# LCDv.net
KiCad netlist of a schematic drawn in EAGLE
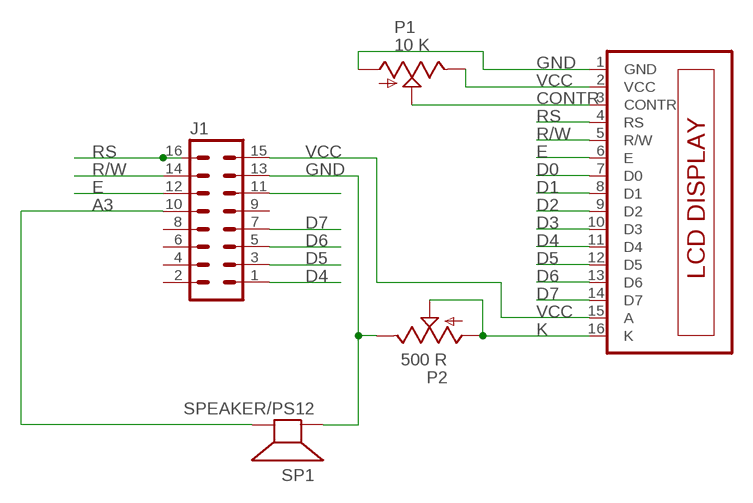
[diagram p0: schematic, sheet 1]

(export (version "E")
  (design (tool "Eeschema 10.0.6"))
  (components
    (comp (ref "J1")
      (value "ML16L")
      (footprint "eagle-import:ML16L")
      (libsource (lib "eagle-import") (part "ML16L"))
    )
    (comp (ref "LCD1")
      (value "DISP_LCD-4X20")
      (footprint "eagle-import:DISP_LCD_4X20")
      (libsource (lib "eagle-import") (part "DISP_LCD-4X20"))
    )
    (comp (ref "P1")
      (value "10 K")
      (footprint "eagle-import:6MM")
      (libsource (lib "eagle-import") (part "TRIM"))
    )
    (comp (ref "P2")
      (value "500 R")
      (footprint "eagle-import:6MM")
      (libsource (lib "eagle-import") (part "TRIM"))
    )
    (comp (ref "SP1")
      (value "SPEAKER/PS12")
      (footprint "eagle-import:PS12")
      (libsource (lib "eagle-import") (part "SPEAKER/PS12"))
    )
  )
  (nets
    (net (code "1") (name "/A3") (class "Default")
      (node (ref "J1") (pin "10") (pinfunction "10_10") (pintype "passive"))
      (node (ref "SP1") (pin "P$2") (pinfunction "-_P$2") (pintype "passive"))
    )
    (net (code "2") (name "/CONTR") (class "Default")
      (node (ref "LCD1") (pin "3") (pinfunction "CONTR_3") (pintype "input"))
      (node (ref "P1") (pin "S") (pinfunction "S_S") (pintype "passive"))
    )
    (net (code "3") (name "/D0") (class "Default")
      (node (ref "LCD1") (pin "7") (pinfunction "D0_7") (pintype "input"))
    )
    (net (code "4") (name "/D1") (class "Default")
      (node (ref "LCD1") (pin "8") (pinfunction "D1_8") (pintype "input"))
    )
    (net (code "5") (name "/D2") (class "Default")
      (node (ref "LCD1") (pin "9") (pinfunction "D2_9") (pintype "input"))
    )
    (net (code "6") (name "/D3") (class "Default")
      (node (ref "LCD1") (pin "10") (pinfunction "D3_10") (pintype "input"))
    )
    (net (code "7") (name "/D4") (class "Default")
      (node (ref "J1") (pin "1") (pinfunction "1_1") (pintype "passive"))
      (node (ref "LCD1") (pin "11") (pinfunction "D4_11") (pintype "input"))
    )
    (net (code "8") (name "/D5") (class "Default")
      (node (ref "J1") (pin "3") (pinfunction "3_3") (pintype "passive"))
      (node (ref "LCD1") (pin "12") (pinfunction "D5_12") (pintype "input"))
    )
    (net (code "9") (name "/D6") (class "Default")
      (node (ref "J1") (pin "5") (pinfunction "5_5") (pintype "passive"))
      (node (ref "LCD1") (pin "13") (pinfunction "D6_13") (pintype "input"))
    )
    (net (code "10") (name "/D7") (class "Default")
      (node (ref "J1") (pin "7") (pinfunction "7_7") (pintype "passive"))
      (node (ref "LCD1") (pin "14") (pinfunction "D7_14") (pintype "input"))
    )
    (net (code "11") (name "/E") (class "Default")
      (node (ref "J1") (pin "12") (pinfunction "12_12") (pintype "passive"))
      (node (ref "LCD1") (pin "6") (pinfunction "E_6") (pintype "input"))
    )
    (net (code "12") (name "/GND") (class "Default")
      (node (ref "J1") (pin "13") (pinfunction "13_13") (pintype "passive"))
      (node (ref "LCD1") (pin "1") (pinfunction "GND_1") (pintype "power_in"))
      (node (ref "P1") (pin "A") (pinfunction "A_A") (pintype "passive"))
      (node (ref "P2") (pin "E") (pinfunction "E_E") (pintype "passive"))
      (node (ref "SP1") (pin "P$1") (pinfunction "+_P$1") (pintype "passive"))
    )
    (net (code "13") (name "/K") (class "Default")
      (node (ref "LCD1") (pin "16") (pinfunction "K_16") (pintype "power_in"))
      (node (ref "P2") (pin "A") (pinfunction "A_A") (pintype "passive"))
      (node (ref "P2") (pin "S") (pinfunction "S_S") (pintype "passive"))
    )
    (net (code "14") (name "/RS") (class "Default")
      (node (ref "J1") (pin "16") (pinfunction "16_16") (pintype "passive"))
      (node (ref "LCD1") (pin "4") (pinfunction "RS_4") (pintype "input"))
    )
    (net (code "15") (name "/R{slash}W") (class "Default")
      (node (ref "J1") (pin "14") (pinfunction "14_14") (pintype "passive"))
      (node (ref "LCD1") (pin "5") (pinfunction "R/W_5") (pintype "input"))
    )
    (net (code "16") (name "/VCC") (class "Default")
      (node (ref "J1") (pin "15") (pinfunction "15_15") (pintype "passive"))
      (node (ref "LCD1") (pin "15") (pinfunction "A_15") (pintype "power_in"))
      (node (ref "LCD1") (pin "2") (pinfunction "VCC_2") (pintype "power_in"))
      (node (ref "P1") (pin "E") (pinfunction "E_E") (pintype "passive"))
    )
    (net (code "17") (name "unconnected-(J1-Pad2)") (class "Default")
      (node (ref "J1") (pin "2") (pinfunction "2_2") (pintype "passive"))
    )
    (net (code "18") (name "unconnected-(J1-Pad4)") (class "Default")
      (node (ref "J1") (pin "4") (pinfunction "4_4") (pintype "passive"))
    )
    (net (code "19") (name "unconnected-(J1-Pad6)") (class "Default")
      (node (ref "J1") (pin "6") (pinfunction "6_6") (pintype "passive"))
    )
    (net (code "20") (name "unconnected-(J1-Pad8)") (class "Default")
      (node (ref "J1") (pin "8") (pinfunction "8_8") (pintype "passive"))
    )
    (net (code "21") (name "unconnected-(J1-Pad9)") (class "Default")
      (node (ref "J1") (pin "9") (pinfunction "9_9") (pintype "passive"))
    )
    (net (code "22") (name "unconnected-(J1-Pad11)") (class "Default")
      (node (ref "J1") (pin "11") (pinfunction "11_11") (pintype "passive"))
    )
  )
)
